# electron_mpu9250_analog_mic.net
KiCad netlist of a schematic drawn in EAGLE
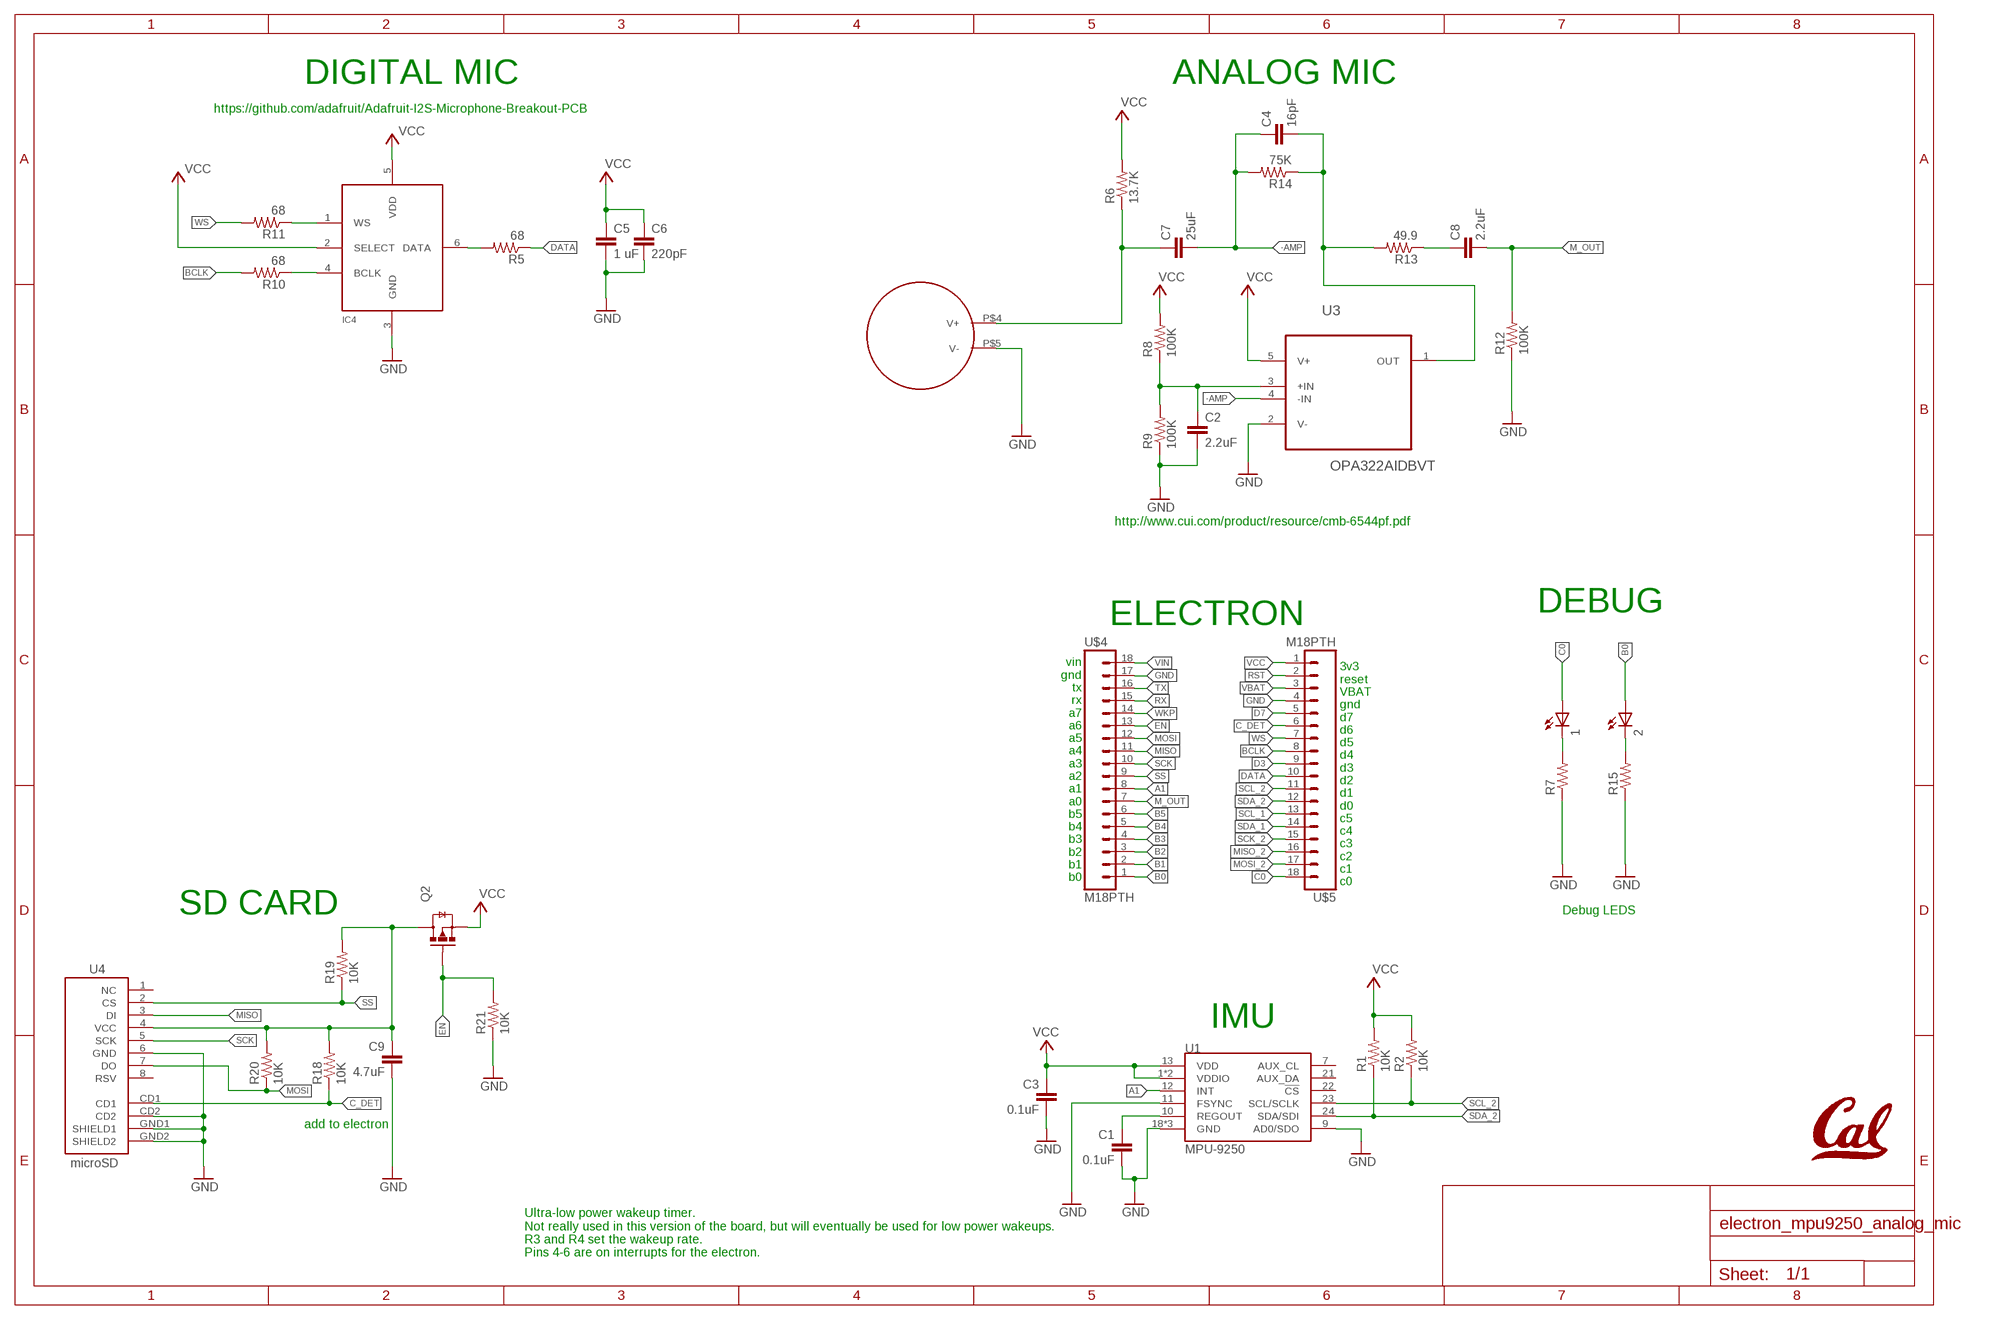
[diagram p0: schematic, sheet 1]

(export (version "E")
  (design (tool "Eeschema 10.0.6"))
  (components
    (comp (ref "1")
      (value "LEDCHIP-LED0603")
      (footprint "eagle-import:CHIP-LED0603")
      (libsource (lib "eagle-import") (part "LEDCHIP-LED0603"))
    )
    (comp (ref "2")
      (value "LEDCHIP-LED0603")
      (footprint "eagle-import:CHIP-LED0603")
      (libsource (lib "eagle-import") (part "LEDCHIP-LED0603"))
    )
    (comp (ref "C1")
      (value "0.1uF")
      (footprint "eagle-import:0603-CAP")
      (libsource (lib "eagle-import") (part "0.1UF-25V(+80/-20%)(0603)"))
    )
    (comp (ref "C2")
      (value "2.2uF")
      (footprint "eagle-import:C0603")
      (libsource (lib "eagle-import") (part "C-EUC0603"))
    )
    (comp (ref "C3")
      (value "0.1uF")
      (footprint "eagle-import:0603-CAP")
      (libsource (lib "eagle-import") (part "0.1UF-25V(+80/-20%)(0603)"))
    )
    (comp (ref "C4")
      (value "16pF")
      (footprint "eagle-import:C0603")
      (libsource (lib "eagle-import") (part "C-EUC0603"))
    )
    (comp (ref "C5")
      (value "1 uF")
      (footprint "eagle-import:C0603")
      (libsource (lib "eagle-import") (part "C-EUC0603"))
    )
    (comp (ref "C6")
      (value "220pF")
      (footprint "eagle-import:C0603")
      (libsource (lib "eagle-import") (part "C-EUC0603"))
    )
    (comp (ref "C7")
      (value "25uF")
      (footprint "eagle-import:C0603")
      (libsource (lib "eagle-import") (part "C-EUC0603"))
    )
    (comp (ref "C8")
      (value "2.2uF")
      (footprint "eagle-import:C0603")
      (libsource (lib "eagle-import") (part "C-EUC0603"))
    )
    (comp (ref "C9")
      (value "4.7uF")
      (footprint "eagle-import:0603-CAP")
      (libsource (lib "eagle-import") (part "0.1UF-25V(+80/-20%)(0603)"))
    )
    (comp (ref "IC4")
      (value "MIC_I2S_SPH0645")
      (footprint "eagle-import:SPH0645LM4H")
      (libsource (lib "eagle-import") (part "MIC_I2S_SPH0645"))
    )
    (comp (ref "L1")
      (value "UCB_CAL100MIL")
      (footprint "eagle-import:UCB_CAL_100MIL")
      (libsource (lib "eagle-import") (part "UCB_CAL100MIL"))
    )
    (comp (ref "Q2")
      (value "NX3008PBK")
      (footprint "eagle-import:SOT23-3")
      (libsource (lib "eagle-import") (part "NX3008PBK"))
    )
    (comp (ref "R1")
      (value "10K")
      (footprint "eagle-import:0603-RES")
      (libsource (lib "eagle-import") (part "10KOHM-1/10W-1%(0603)0603"))
    )
    (comp (ref "R2")
      (value "10K")
      (footprint "eagle-import:0603-RES")
      (libsource (lib "eagle-import") (part "10KOHM-1/10W-1%(0603)0603"))
    )
    (comp (ref "R5")
      (value "68")
      (footprint "eagle-import:R0603")
      (libsource (lib "eagle-import") (part "R-US_R0603"))
    )
    (comp (ref "R6")
      (value "13.7K")
      (footprint "eagle-import:R0603")
      (libsource (lib "eagle-import") (part "R-US_R0603"))
    )
    (comp (ref "R7")
      (value "R-US_R0603")
      (footprint "eagle-import:R0603")
      (libsource (lib "eagle-import") (part "R-US_R0603"))
    )
    (comp (ref "R8")
      (value "100K")
      (footprint "eagle-import:R0603")
      (libsource (lib "eagle-import") (part "R-US_R0603"))
    )
    (comp (ref "R9")
      (value "100K")
      (footprint "eagle-import:R0603")
      (libsource (lib "eagle-import") (part "R-US_R0603"))
    )
    (comp (ref "R10")
      (value "68")
      (footprint "eagle-import:R0603")
      (libsource (lib "eagle-import") (part "R-US_R0603"))
    )
    (comp (ref "R11")
      (value "68")
      (footprint "eagle-import:R0603")
      (libsource (lib "eagle-import") (part "R-US_R0603"))
    )
    (comp (ref "R12")
      (value "100K")
      (footprint "eagle-import:R0603")
      (libsource (lib "eagle-import") (part "R-US_R0603"))
    )
    (comp (ref "R13")
      (value "49.9")
      (footprint "eagle-import:R0603")
      (libsource (lib "eagle-import") (part "R-US_R0603"))
    )
    (comp (ref "R14")
      (value "75K")
      (footprint "eagle-import:R0603")
      (libsource (lib "eagle-import") (part "R-US_R0603"))
    )
    (comp (ref "R15")
      (value "R-US_R0603")
      (footprint "eagle-import:R0603")
      (libsource (lib "eagle-import") (part "R-US_R0603"))
    )
    (comp (ref "R18")
      (value "10K")
      (footprint "eagle-import:R0603")
      (libsource (lib "eagle-import") (part "R-US_R0603"))
    )
    (comp (ref "R19")
      (value "10K")
      (footprint "eagle-import:R0603")
      (libsource (lib "eagle-import") (part "R-US_R0603"))
    )
    (comp (ref "R20")
      (value "10K")
      (footprint "eagle-import:R0603")
      (libsource (lib "eagle-import") (part "R-US_R0603"))
    )
    (comp (ref "R21")
      (value "10K")
      (footprint "eagle-import:R0603")
      (libsource (lib "eagle-import") (part "R-US_R0603"))
    )
    (comp (ref "U$1")
      (value "CMB-6544PF")
      (footprint "eagle-import:CMB-6544PF")
      (libsource (lib "eagle-import") (part "CMB-6544PF"))
    )
    (comp (ref "U$4")
      (value "M18PTH")
      (footprint "eagle-import:1X18-SMALL-PADS")
      (libsource (lib "eagle-import") (part "M18PTH"))
    )
    (comp (ref "U$5")
      (value "M18PTH")
      (footprint "eagle-import:1X18-SMALL-PADS")
      (libsource (lib "eagle-import") (part "M18PTH"))
    )
    (comp (ref "U1")
      (value "MPU-9250")
      (footprint "eagle-import:QFN24_PAD")
      (libsource (lib "eagle-import") (part "MPU-9250"))
    )
    (comp (ref "U3")
      (value "OPA322AIDBVT")
      (footprint "eagle-import:SOT95P280X145-5N")
      (fields (field (name "MF") "Texas Instruments"))
      (libsource (lib "eagle-import") (part "OPA322AIDBVT"))
    )
    (comp (ref "U4")
      (value "microSD")
      (footprint "eagle-import:MICRO-SD-SOCKET-PP")
      (libsource (lib "eagle-import") (part "USD-SOCKETSMD"))
    )
  )
  (nets
    (net (code "1") (name "-AMP") (class "Default")
      (node (ref "C4") (pin "1") (pinfunction "1_1") (pintype "passive"))
      (node (ref "C7") (pin "2") (pinfunction "2_2") (pintype "passive"))
      (node (ref "R14") (pin "2") (pinfunction "2_2") (pintype "passive"))
      (node (ref "U3") (pin "4") (pinfunction "-IN_4") (pintype "input"))
    )
    (net (code "2") (name "A1") (class "Default")
      (node (ref "U$4") (pin "8") (pinfunction "8_8") (pintype "passive"))
      (node (ref "U1") (pin "12") (pinfunction "INT_12") (pintype "bidirectional"))
    )
    (net (code "3") (name "B0") (class "Default")
      (node (ref "2") (pin "A") (pinfunction "A_A") (pintype "passive"))
      (node (ref "U$4") (pin "1") (pinfunction "1_1") (pintype "passive"))
    )
    (net (code "4") (name "B1") (class "Default")
      (node (ref "U$4") (pin "2") (pinfunction "2_2") (pintype "passive"))
    )
    (net (code "5") (name "B2") (class "Default")
      (node (ref "U$4") (pin "3") (pinfunction "3_3") (pintype "passive"))
    )
    (net (code "6") (name "B3") (class "Default")
      (node (ref "U$4") (pin "4") (pinfunction "4_4") (pintype "passive"))
    )
    (net (code "7") (name "B4") (class "Default")
      (node (ref "U$4") (pin "5") (pinfunction "5_5") (pintype "passive"))
    )
    (net (code "8") (name "B5") (class "Default")
      (node (ref "U$4") (pin "6") (pinfunction "6_6") (pintype "passive"))
    )
    (net (code "9") (name "BCLK") (class "Default")
      (node (ref "R10") (pin "2") (pinfunction "2_2") (pintype "passive"))
      (node (ref "U$5") (pin "8") (pinfunction "8_8") (pintype "passive"))
    )
    (net (code "10") (name "C0") (class "Default")
      (node (ref "1") (pin "A") (pinfunction "A_A") (pintype "passive"))
      (node (ref "U$5") (pin "18") (pinfunction "18_18") (pintype "passive"))
    )
    (net (code "11") (name "C_DET") (class "Default")
      (node (ref "R18") (pin "1") (pinfunction "1_1") (pintype "passive"))
      (node (ref "U$5") (pin "6") (pinfunction "6_6") (pintype "passive"))
      (node (ref "U4") (pin "CD1") (pinfunction "CD1_CD1") (pintype "bidirectional"))
    )
    (net (code "12") (name "D3") (class "Default")
      (node (ref "U$5") (pin "9") (pinfunction "9_9") (pintype "passive"))
    )
    (net (code "13") (name "D7") (class "Default")
      (node (ref "U$5") (pin "5") (pinfunction "5_5") (pintype "passive"))
    )
    (net (code "14") (name "DATA") (class "Default")
      (node (ref "R5") (pin "1") (pinfunction "1_1") (pintype "passive"))
      (node (ref "U$5") (pin "10") (pinfunction "10_10") (pintype "passive"))
    )
    (net (code "15") (name "EN") (class "Default")
      (node (ref "Q2") (pin "1") (pinfunction "G_1") (pintype "passive"))
      (node (ref "R21") (pin "2") (pinfunction "2_2") (pintype "passive"))
      (node (ref "U$4") (pin "13") (pinfunction "13_13") (pintype "passive"))
    )
    (net (code "16") (name "GND") (class "Default")
      (node (ref "C1") (pin "2") (pinfunction "2_2") (pintype "passive"))
      (node (ref "C2") (pin "2") (pinfunction "2_2") (pintype "passive"))
      (node (ref "C3") (pin "2") (pinfunction "2_2") (pintype "passive"))
      (node (ref "C5") (pin "2") (pinfunction "2_2") (pintype "passive"))
      (node (ref "C6") (pin "2") (pinfunction "2_2") (pintype "passive"))
      (node (ref "C9") (pin "2") (pinfunction "2_2") (pintype "passive"))
      (node (ref "IC4") (pin "3") (pinfunction "GND_3") (pintype "power_in"))
      (node (ref "R12") (pin "1") (pinfunction "1_1") (pintype "passive"))
      (node (ref "R15") (pin "1") (pinfunction "1_1") (pintype "passive"))
      (node (ref "R21") (pin "1") (pinfunction "1_1") (pintype "passive"))
      (node (ref "R7") (pin "1") (pinfunction "1_1") (pintype "passive"))
      (node (ref "R9") (pin "1") (pinfunction "1_1") (pintype "passive"))
      (node (ref "U$1") (pin "P$5") (pinfunction "V-_P$5") (pintype "bidirectional"))
      (node (ref "U$4") (pin "17") (pinfunction "17_17") (pintype "passive"))
      (node (ref "U$5") (pin "4") (pinfunction "4_4") (pintype "passive"))
      (node (ref "U1") (pin "11") (pinfunction "FSYNC_11") (pintype "bidirectional"))
      (node (ref "U1") (pin "18") (pinfunction "GND_18") (pintype "bidirectional"))
      (node (ref "U1") (pin "20") (pinfunction "GND_20") (pintype "bidirectional"))
      (node (ref "U1") (pin "9") (pinfunction "AD0/SDO_9") (pintype "bidirectional"))
      (node (ref "U1") (pin "CENTER") (pinfunction "GND_CENTER") (pintype "bidirectional"))
      (node (ref "U3") (pin "2") (pinfunction "V-_2") (pintype "passive"))
      (node (ref "U4") (pin "6") (pinfunction "GND_6") (pintype "bidirectional"))
      (node (ref "U4") (pin "CD2") (pinfunction "CD2_CD2") (pintype "bidirectional"))
      (node (ref "U4") (pin "GND1") (pinfunction "SHIELD1_GND1") (pintype "bidirectional"))
      (node (ref "U4") (pin "GND2") (pinfunction "SHIELD2_GND2") (pintype "bidirectional"))
    )
    (net (code "17") (name "MISO") (class "Default")
      (node (ref "U$4") (pin "11") (pinfunction "11_11") (pintype "passive"))
      (node (ref "U4") (pin "3") (pinfunction "DI_3") (pintype "bidirectional"))
    )
    (net (code "18") (name "MISO_2") (class "Default")
      (node (ref "U$5") (pin "16") (pinfunction "16_16") (pintype "passive"))
    )
    (net (code "19") (name "MOSI") (class "Default")
      (node (ref "R20") (pin "1") (pinfunction "1_1") (pintype "passive"))
      (node (ref "U$4") (pin "12") (pinfunction "12_12") (pintype "passive"))
      (node (ref "U4") (pin "7") (pinfunction "DO_7") (pintype "bidirectional"))
    )
    (net (code "20") (name "MOSI_2") (class "Default")
      (node (ref "U$5") (pin "17") (pinfunction "17_17") (pintype "passive"))
    )
    (net (code "21") (name "M_OUT") (class "Default")
      (node (ref "C8") (pin "2") (pinfunction "2_2") (pintype "passive"))
      (node (ref "R12") (pin "2") (pinfunction "2_2") (pintype "passive"))
      (node (ref "U$4") (pin "7") (pinfunction "7_7") (pintype "passive"))
    )
    (net (code "22") (name "Net-(1-PadC)") (class "Default")
      (node (ref "1") (pin "C") (pinfunction "C_C") (pintype "passive"))
      (node (ref "R7") (pin "2") (pinfunction "2_2") (pintype "passive"))
    )
    (net (code "23") (name "Net-(2-PadC)") (class "Default")
      (node (ref "2") (pin "C") (pinfunction "C_C") (pintype "passive"))
      (node (ref "R15") (pin "2") (pinfunction "2_2") (pintype "passive"))
    )
    (net (code "24") (name "Net-(C8-Pad1)") (class "Default")
      (node (ref "C8") (pin "1") (pinfunction "1_1") (pintype "passive"))
      (node (ref "R13") (pin "1") (pinfunction "1_1") (pintype "passive"))
    )
    (net (code "25") (name "Net-(IC4-BCLK)") (class "Default")
      (node (ref "IC4") (pin "4") (pinfunction "BCLK_4") (pintype "input"))
      (node (ref "R10") (pin "1") (pinfunction "1_1") (pintype "passive"))
    )
    (net (code "26") (name "Net-(IC4-DATA)") (class "Default")
      (node (ref "IC4") (pin "6") (pinfunction "DATA_6") (pintype "output"))
      (node (ref "R5") (pin "2") (pinfunction "2_2") (pintype "passive"))
    )
    (net (code "27") (name "Net-(IC4-WS)") (class "Default")
      (node (ref "IC4") (pin "1") (pinfunction "WS_1") (pintype "input"))
      (node (ref "R11") (pin "1") (pinfunction "1_1") (pintype "passive"))
    )
    (net (code "28") (name "Net-(Q2-D)") (class "Default")
      (node (ref "C9") (pin "1") (pinfunction "1_1") (pintype "passive"))
      (node (ref "Q2") (pin "3") (pinfunction "D_3") (pintype "passive"))
      (node (ref "R18") (pin "2") (pinfunction "2_2") (pintype "passive"))
      (node (ref "R19") (pin "2") (pinfunction "2_2") (pintype "passive"))
      (node (ref "R20") (pin "2") (pinfunction "2_2") (pintype "passive"))
      (node (ref "U4") (pin "4") (pinfunction "VCC_4") (pintype "bidirectional"))
    )
    (net (code "29") (name "Net-(U$1-V+)") (class "Default")
      (node (ref "C7") (pin "1") (pinfunction "1_1") (pintype "passive"))
      (node (ref "R6") (pin "1") (pinfunction "1_1") (pintype "passive"))
      (node (ref "U$1") (pin "P$4") (pinfunction "V+_P$4") (pintype "bidirectional"))
    )
    (net (code "30") (name "Net-(U1-REGOUT)") (class "Default")
      (node (ref "C1") (pin "1") (pinfunction "1_1") (pintype "passive"))
      (node (ref "U1") (pin "10") (pinfunction "REGOUT_10") (pintype "bidirectional"))
    )
    (net (code "31") (name "Net-(U3-+IN)") (class "Default")
      (node (ref "C2") (pin "1") (pinfunction "1_1") (pintype "passive"))
      (node (ref "R8") (pin "1") (pinfunction "1_1") (pintype "passive"))
      (node (ref "R9") (pin "2") (pinfunction "2_2") (pintype "passive"))
      (node (ref "U3") (pin "3") (pinfunction "+IN_3") (pintype "input"))
    )
    (net (code "32") (name "Net-(U3-OUT)") (class "Default")
      (node (ref "C4") (pin "2") (pinfunction "2_2") (pintype "passive"))
      (node (ref "R13") (pin "2") (pinfunction "2_2") (pintype "passive"))
      (node (ref "R14") (pin "1") (pinfunction "1_1") (pintype "passive"))
      (node (ref "U3") (pin "1") (pinfunction "OUT_1") (pintype "output"))
    )
    (net (code "33") (name "RST") (class "Default")
      (node (ref "U$5") (pin "2") (pinfunction "2_2") (pintype "passive"))
    )
    (net (code "34") (name "RX") (class "Default")
      (node (ref "U$4") (pin "15") (pinfunction "15_15") (pintype "passive"))
    )
    (net (code "35") (name "SCK") (class "Default")
      (node (ref "U$4") (pin "10") (pinfunction "10_10") (pintype "passive"))
      (node (ref "U4") (pin "5") (pinfunction "SCK_5") (pintype "bidirectional"))
    )
    (net (code "36") (name "SCK_2") (class "Default")
      (node (ref "U$5") (pin "15") (pinfunction "15_15") (pintype "passive"))
    )
    (net (code "37") (name "SCL_1") (class "Default")
      (node (ref "U$5") (pin "13") (pinfunction "13_13") (pintype "passive"))
    )
    (net (code "38") (name "SCL_2") (class "Default")
      (node (ref "R2") (pin "1") (pinfunction "1_1") (pintype "passive"))
      (node (ref "U$5") (pin "11") (pinfunction "11_11") (pintype "passive"))
      (node (ref "U1") (pin "23") (pinfunction "SCL/SCLK_23") (pintype "bidirectional"))
    )
    (net (code "39") (name "SDA_1") (class "Default")
      (node (ref "U$5") (pin "14") (pinfunction "14_14") (pintype "passive"))
    )
    (net (code "40") (name "SDA_2") (class "Default")
      (node (ref "R1") (pin "1") (pinfunction "1_1") (pintype "passive"))
      (node (ref "U$5") (pin "12") (pinfunction "12_12") (pintype "passive"))
      (node (ref "U1") (pin "24") (pinfunction "SDA/SDI_24") (pintype "bidirectional"))
    )
    (net (code "41") (name "SS") (class "Default")
      (node (ref "R19") (pin "1") (pinfunction "1_1") (pintype "passive"))
      (node (ref "U$4") (pin "9") (pinfunction "9_9") (pintype "passive"))
      (node (ref "U4") (pin "2") (pinfunction "CS_2") (pintype "bidirectional"))
    )
    (net (code "42") (name "TX") (class "Default")
      (node (ref "U$4") (pin "16") (pinfunction "16_16") (pintype "passive"))
    )
    (net (code "43") (name "VBAT") (class "Default")
      (node (ref "U$5") (pin "3") (pinfunction "3_3") (pintype "passive"))
    )
    (net (code "44") (name "VCC") (class "Default")
      (node (ref "C3") (pin "1") (pinfunction "1_1") (pintype "passive"))
      (node (ref "C5") (pin "1") (pinfunction "1_1") (pintype "passive"))
      (node (ref "C6") (pin "1") (pinfunction "1_1") (pintype "passive"))
      (node (ref "IC4") (pin "2") (pinfunction "SELECT_2") (pintype "input"))
      (node (ref "IC4") (pin "5") (pinfunction "VDD_5") (pintype "power_in"))
      (node (ref "Q2") (pin "2") (pinfunction "S_2") (pintype "passive"))
      (node (ref "R1") (pin "2") (pinfunction "2_2") (pintype "passive"))
      (node (ref "R2") (pin "2") (pinfunction "2_2") (pintype "passive"))
      (node (ref "R6") (pin "2") (pinfunction "2_2") (pintype "passive"))
      (node (ref "R8") (pin "2") (pinfunction "2_2") (pintype "passive"))
      (node (ref "U$5") (pin "1") (pinfunction "1_1") (pintype "passive"))
      (node (ref "U1") (pin "1") (pinfunction "VDDIO_1") (pintype "bidirectional"))
      (node (ref "U1") (pin "13") (pinfunction "VDD_13") (pintype "bidirectional"))
      (node (ref "U1") (pin "8") (pinfunction "VDDIO_8") (pintype "bidirectional"))
      (node (ref "U3") (pin "5") (pinfunction "V+_5") (pintype "power_in"))
    )
    (net (code "45") (name "VIN") (class "Default")
      (node (ref "U$4") (pin "18") (pinfunction "18_18") (pintype "passive"))
    )
    (net (code "46") (name "WKP") (class "Default")
      (node (ref "U$4") (pin "14") (pinfunction "14_14") (pintype "passive"))
    )
    (net (code "47") (name "WS") (class "Default")
      (node (ref "R11") (pin "2") (pinfunction "2_2") (pintype "passive"))
      (node (ref "U$5") (pin "7") (pinfunction "7_7") (pintype "passive"))
    )
    (net (code "48") (name "unconnected-(U1-AUX_CL-Pad7)") (class "Default")
      (node (ref "U1") (pin "7") (pinfunction "AUX_CL_7") (pintype "bidirectional"))
    )
    (net (code "49") (name "unconnected-(U1-AUX_DA-Pad21)") (class "Default")
      (node (ref "U1") (pin "21") (pinfunction "AUX_DA_21") (pintype "bidirectional"))
    )
    (net (code "50") (name "unconnected-(U1-~{CS}-Pad22)") (class "Default")
      (node (ref "U1") (pin "22") (pinfunction "~{CS}_22") (pintype "bidirectional"))
    )
    (net (code "51") (name "unconnected-(U4-NC-Pad1)") (class "Default")
      (node (ref "U4") (pin "1") (pinfunction "NC_1") (pintype "bidirectional"))
    )
    (net (code "52") (name "unconnected-(U4-RSV-Pad8)") (class "Default")
      (node (ref "U4") (pin "8") (pinfunction "RSV_8") (pintype "bidirectional"))
    )
  )
)
